# MicroSpecSensorBoard_PowerSupply_V2_1.net
KiCad netlist of a schematic drawn in Altium Designer
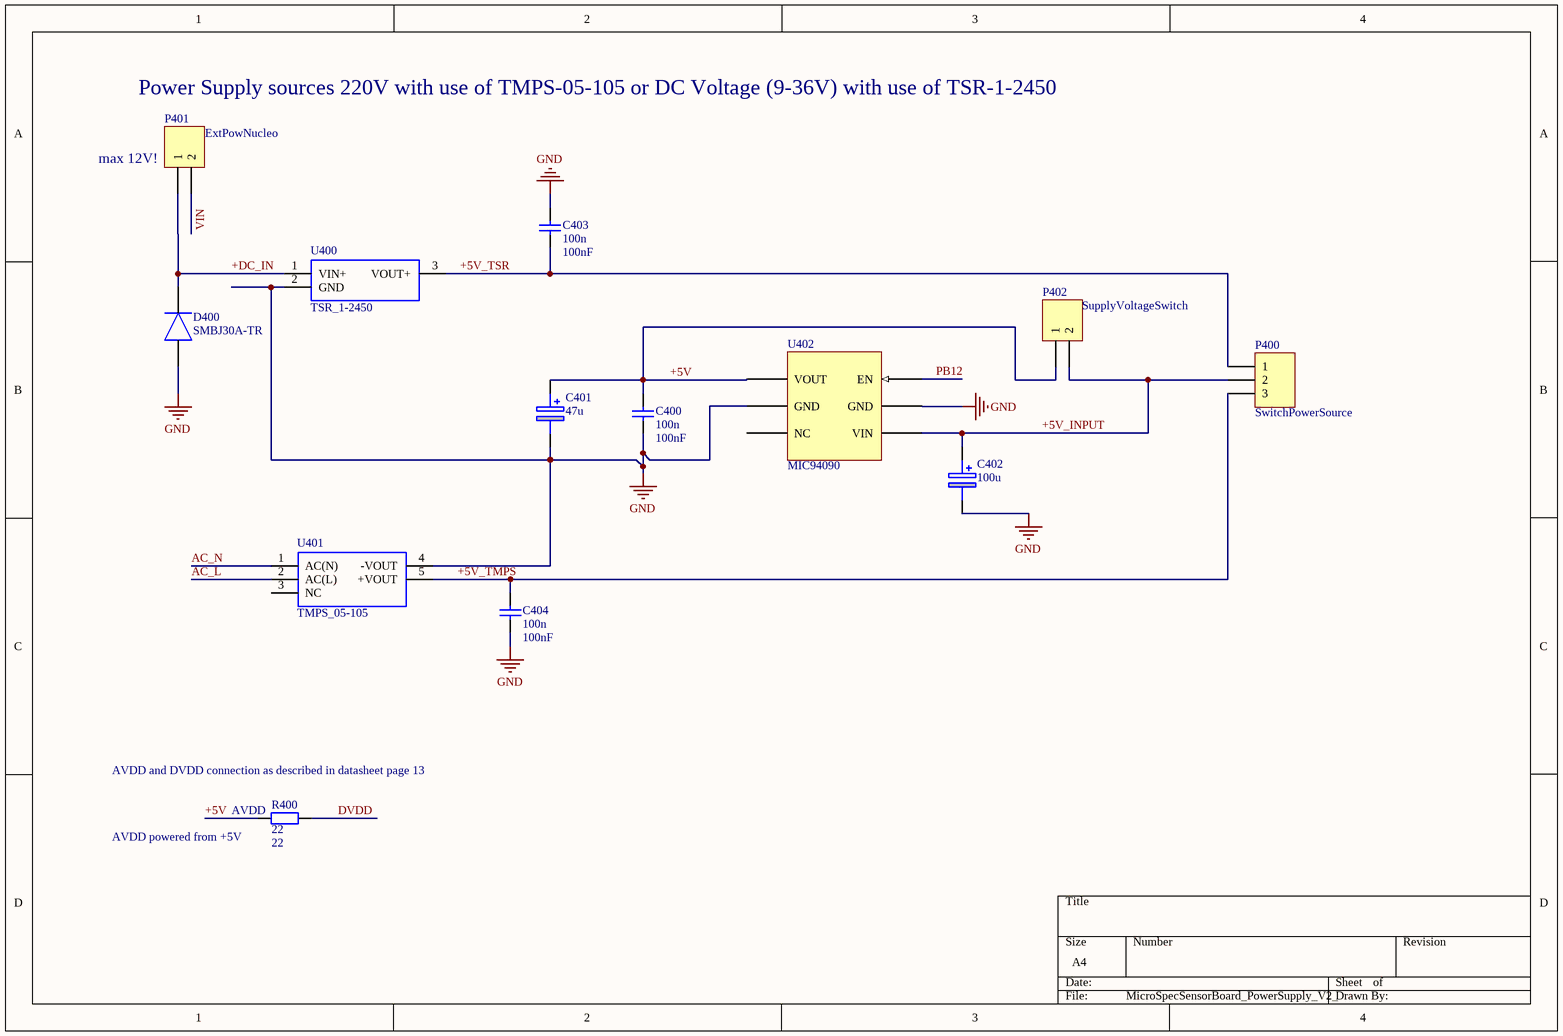
[diagram p0: MicroSpecSensorBoard_PowerSupply_V2_1.SchDoc]

(export (version "E")
  (design (tool "Eeschema 10.0.6"))
  (components
    (comp (ref "C400")
      (value "100n")
      (footprint "6-0805_L")
      (description "Capacitor")
      (fields (field (name "ALTIUM_VALUE") "100nF") (field (name "PUBLISHER") "Altium Limited"))
      (libsource (lib "USER_Library") (part "Cap"))
    )
    (comp (ref "C401")
      (value "47u")
      (footprint "FKV(D)")
      (description "Ecap 47F 63V")
      (fields
        (field (name "RS PART NUMBER") "7083588P")
        (field (name "MANUFACTURER_PART_NUMBER") "EEEFK1J100P")
      )
      (libsource (lib "USER_Library") (part "EEEFK1J100P"))
    )
    (comp (ref "C402")
      (value "100u")
      (footprint "FKV(D)")
      (description "Ecap 100uF 63V")
      (fields
        (field (name "RS PART NUMBER") "7083588P")
        (field (name "MANUFACTURER_PART_NUMBER") "EEEFK1J100P")
      )
      (libsource (lib "USER_Library") (part "EEEFK1J100P"))
    )
    (comp (ref "C403")
      (value "100n")
      (footprint "6-0805_L")
      (description "Capacitor")
      (fields (field (name "ALTIUM_VALUE") "100nF") (field (name "PUBLISHER") "Altium Limited"))
      (libsource (lib "USER_Library") (part "Cap"))
    )
    (comp (ref "C404")
      (value "100n")
      (footprint "6-0805_L")
      (description "Capacitor")
      (fields (field (name "ALTIUM_VALUE") "100nF") (field (name "PUBLISHER") "Altium Limited"))
      (libsource (lib "USER_Library") (part "Cap"))
    )
    (comp (ref "D400")
      (value "SMBJ30A-TR")
      (footprint "DIOM5436X265N")
      (description "TVS Diode Uni-Directional SMBJ30A-TR 64.3V, 600W, SMB 2-Pin")
      (fields (field (name "RS PART NUMBER") "7141048P"))
      (libsource (lib "USER_Library") (part "SMBJ30A-TR"))
    )
    (comp (ref "P400")
      (value "SwitchPowerSource")
      (footprint "HDR1X3")
      (description "Header, 3-Pin")
      (fields (field (name "PUBLISHER") "Altium Limited"))
      (libsource (lib "Miscellaneous Connectors") (part "Header 3"))
    )
    (comp (ref "P401")
      (value "ExtPowNucleo")
      (footprint "HDR1X2")
      (description "Header, 2-Pin")
      (fields (field (name "PUBLISHER") "Altium Limited"))
      (libsource (lib "Miscellaneous Connectors") (part "Header 2"))
    )
    (comp (ref "P402")
      (value "SupplyVoltageSwitch")
      (footprint "HDR1X2")
      (description "Header, 2-Pin")
      (fields (field (name "PUBLISHER") "Altium Limited"))
      (libsource (lib "Miscellaneous Connectors") (part "Header 2"))
    )
    (comp (ref "R400")
      (value "22")
      (footprint "6-0805_L")
      (description "Resistor")
      (fields (field (name "ALTIUM_VALUE") "22") (field (name "PUBLISHER") "Altium Limited"))
      (libsource (lib "USER_Library") (part "Res2"))
    )
    (comp (ref "U400")
      (value "TSR_1-2450")
      (footprint "TSR-1-24120")
      (description "Switching Regulator,6.5-32Vin,5Vout 1A Switching Regulator, 6.5 ??? 36V dc Input, 5V Output, 1A")
      (fields
        (field (name "RS PART NUMBER") "6664379P")
        (field (name "MANUFACTURER_PART_NUMBER") "TSR 1-2450")
      )
      (libsource (lib "USER_Library") (part "TSR_1-2450"))
    )
    (comp (ref "U401")
      (value "TMPS_05-105")
      (footprint "TMPS05-105")
      (description "AC/DC Power Modules 5W 5Vdc 1000mA AC/DC Power module")
      (fields
        (field (name "MANUFACTURER_PART_NUMBER") "TMPS 05-105")
        (field (name "RS PART NUMBER") "8920630")
      )
      (libsource (lib "USER_Library") (part "TMPS_05-105"))
    )
    (comp (ref "U402")
      (value "MIC94090")
      (footprint "SOT65P210X110-6N")
      (description "high side switch")
      (libsource (lib "USER_Library") (part "MIC94090"))
    )
  )
  (nets
    (net (code "1") (name "/+5V") (class "Default")
      (node (ref "C400") (pin "1") (pinfunction "1_1") (pintype "passive"))
      (node (ref "C401") (pin "1") (pinfunction "+_1") (pintype "passive"))
      (node (ref "P402") (pin "1") (pinfunction "1_1") (pintype "passive"))
      (node (ref "R400") (pin "1") (pinfunction "1_1") (pintype "passive"))
      (node (ref "U402") (pin "1") (pinfunction "VOUT_1") (pintype "power_in"))
    )
    (net (code "2") (name "/+5V_INPUT") (class "Default")
      (node (ref "C402") (pin "1") (pinfunction "+_1") (pintype "passive"))
      (node (ref "P400") (pin "2") (pinfunction "2_2") (pintype "passive"))
      (node (ref "P402") (pin "2") (pinfunction "2_2") (pintype "passive"))
      (node (ref "U402") (pin "4") (pinfunction "VIN_4") (pintype "power_in"))
    )
    (net (code "3") (name "/+5V_TMPS") (class "Default")
      (node (ref "C404") (pin "1") (pinfunction "1_1") (pintype "passive"))
      (node (ref "P400") (pin "3") (pinfunction "3_3") (pintype "passive"))
      (node (ref "U401") (pin "5") (pinfunction "+VOUT_5") (pintype "passive"))
    )
    (net (code "4") (name "/+5V_TSR") (class "Default")
      (node (ref "C403") (pin "2") (pinfunction "2_2") (pintype "passive"))
      (node (ref "P400") (pin "1") (pinfunction "1_1") (pintype "passive"))
      (node (ref "U400") (pin "3") (pinfunction "VOUT+_3") (pintype "passive"))
    )
    (net (code "5") (name "/+DC_IN") (class "Default")
      (node (ref "D400") (pin "1") (pinfunction "K_1") (pintype "passive"))
      (node (ref "P401") (pin "1") (pinfunction "1_1") (pintype "passive"))
      (node (ref "U400") (pin "1") (pinfunction "VIN+_1") (pintype "passive"))
    )
    (net (code "6") (name "/AC_L") (class "Default")
      (node (ref "U401") (pin "2") (pinfunction "AC(L)_2") (pintype "passive"))
    )
    (net (code "7") (name "/AC_N") (class "Default")
      (node (ref "U401") (pin "1") (pinfunction "AC(N)_1") (pintype "passive"))
    )
    (net (code "8") (name "/DVDD") (class "Default")
      (node (ref "R400") (pin "2") (pinfunction "2_2") (pintype "passive"))
    )
    (net (code "9") (name "/PB12") (class "Default")
      (node (ref "U402") (pin "6") (pinfunction "EN_6") (pintype "input"))
    )
    (net (code "10") (name "/VIN") (class "Default")
      (node (ref "P401") (pin "2") (pinfunction "2_2") (pintype "passive"))
    )
    (net (code "11") (name "GND") (class "Default")
      (node (ref "C400") (pin "2") (pinfunction "2_2") (pintype "passive"))
      (node (ref "C401") (pin "2") (pinfunction "-_2") (pintype "passive"))
      (node (ref "C402") (pin "2") (pinfunction "-_2") (pintype "passive"))
      (node (ref "C403") (pin "1") (pinfunction "1_1") (pintype "passive"))
      (node (ref "C404") (pin "2") (pinfunction "2_2") (pintype "passive"))
      (node (ref "D400") (pin "2") (pinfunction "A_2") (pintype "passive"))
      (node (ref "U400") (pin "2") (pinfunction "GND_2") (pintype "passive"))
      (node (ref "U401") (pin "4") (pinfunction "-VOUT_4") (pintype "passive"))
      (node (ref "U402") (pin "2") (pinfunction "GND_2") (pintype "power_in"))
      (node (ref "U402") (pin "5") (pinfunction "GND_5") (pintype "power_in"))
    )
    (net (code "12") (name "unconnected-(U401-NC-Pad3)") (class "Default")
      (node (ref "U401") (pin "3") (pinfunction "NC_3") (pintype "passive"))
    )
    (net (code "13") (name "unconnected-(U402-NC-Pad3)") (class "Default")
      (node (ref "U402") (pin "3") (pinfunction "NC_3") (pintype "passive"))
    )
  )
)
